# 3_BackBone.net
KiCad netlist of a schematic drawn in Altium Designer
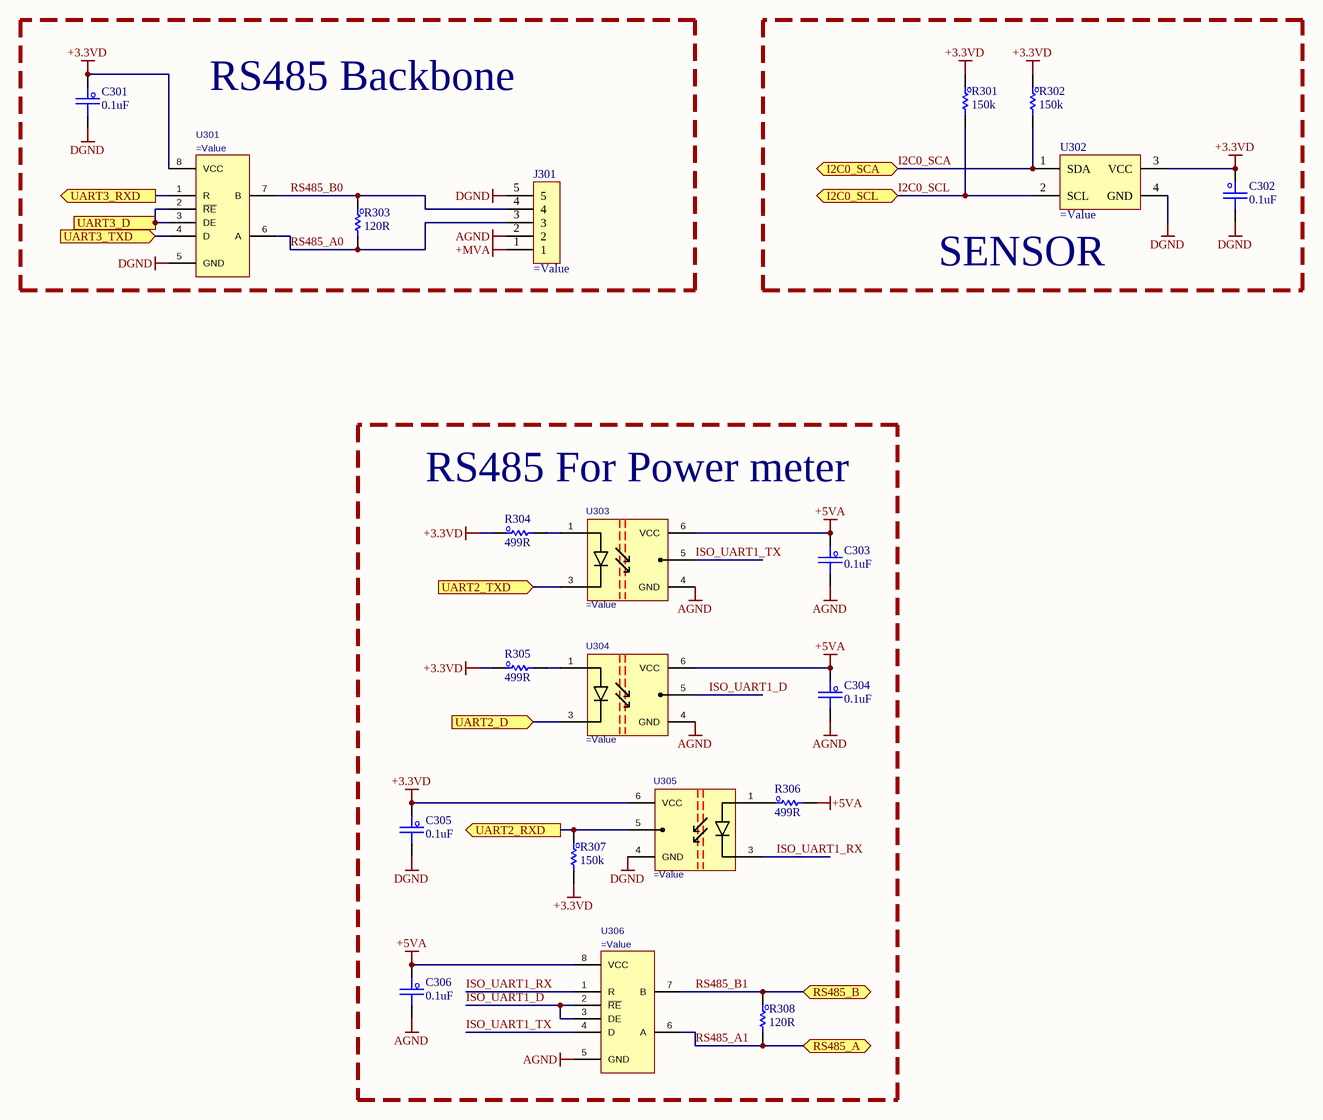
[diagram p0: 3_BackBone.SchDoc]

(export (version "E")
  (design (tool "Eeschema 10.0.6"))
  (components
    (comp (ref "C301")
      (value "0.1uF")
      (footprint "C_0603")
      (description "CAP CER 0.1UF 50V X7R 0603")
      (fields (field (name "MANUFACTURER") "KEMET") (field (name "PARTNUMBER") "C0603C104K5RACTU"))
      (libsource (lib "UUSymbol") (part "C_Capacitor"))
    )
    (comp (ref "C302")
      (value "0.1uF")
      (footprint "C_0603")
      (description "CAP CER 0.1UF 50V X7R 0603")
      (fields (field (name "MANUFACTURER") "KEMET") (field (name "PARTNUMBER") "C0603C104K5RACTU"))
      (libsource (lib "UUSymbol") (part "C_Capacitor"))
    )
    (comp (ref "C303")
      (value "0.1uF")
      (footprint "C_0603")
      (description "CAP CER 0.1UF 50V X7R 0603")
      (fields (field (name "MANUFACTURER") "KEMET") (field (name "PARTNUMBER") "C0603C104K5RACTU"))
      (libsource (lib "UUSymbol") (part "C_Capacitor"))
    )
    (comp (ref "C304")
      (value "0.1uF")
      (footprint "C_0603")
      (description "CAP CER 0.1UF 50V X7R 0603")
      (fields (field (name "MANUFACTURER") "KEMET") (field (name "PARTNUMBER") "C0603C104K5RACTU"))
      (libsource (lib "UUSymbol") (part "C_Capacitor"))
    )
    (comp (ref "C305")
      (value "0.1uF")
      (footprint "C_0603")
      (description "CAP CER 0.1UF 50V X7R 0603")
      (fields (field (name "MANUFACTURER") "KEMET") (field (name "PARTNUMBER") "C0603C104K5RACTU"))
      (libsource (lib "UUSymbol") (part "C_Capacitor"))
    )
    (comp (ref "C306")
      (value "0.1uF")
      (footprint "C_0603")
      (description "CAP CER 0.1UF 50V X7R 0603")
      (fields (field (name "MANUFACTURER") "KEMET") (field (name "PARTNUMBER") "C0603C104K5RACTU"))
      (libsource (lib "UUSymbol") (part "C_Capacitor"))
    )
    (comp (ref "J301")
      (value "~")
      (footprint "CON_9155005541006")
      (description "CONN SPRING BATTERY 5POS R/A SMD")
      (fields (field (name "PARTNUMBER") "009155005541006") (field (name "MANUFACTURER") "AVX"))
      (libsource (lib "UUSymbol") (part "CON_5P_9155005541006"))
    )
    (comp (ref "R301")
      (value "150k")
      (footprint "R_0603")
      (description "RES SMD 150K OHM 1% 1/10W 0603")
      (fields (field (name "MANUFACTURER") "Vishay Dale") (field (name "PARTNUMBER") "CRCW0603150KFKEAC"))
      (libsource (lib "UUSymbol") (part "R_Resister"))
    )
    (comp (ref "R302")
      (value "150k")
      (footprint "R_0603")
      (description "RES SMD 150K OHM 1% 1/10W 0603")
      (fields (field (name "MANUFACTURER") "Vishay Dale") (field (name "PARTNUMBER") "CRCW0603150KFKEAC"))
      (libsource (lib "UUSymbol") (part "R_Resister"))
    )
    (comp (ref "R303")
      (value "120R")
      (footprint "R_0603")
      (description "RES SMD 120 OHM 1% 1/3W 0603")
      (fields (field (name "MANUFACTURER") "Vishay Dale") (field (name "PARTNUMBER") "CRCW0603120RFKEAHP"))
      (libsource (lib "UUSymbol") (part "R_Resister"))
    )
    (comp (ref "R304")
      (value "499R")
      (footprint "R_0603")
      (description "RES 499 OHM 1% 1/10W 0603")
      (fields (field (name "MANUFACTURER") "Vishay Dale") (field (name "PARTNUMBER") "CRCW0603499RFKEAC"))
      (libsource (lib "UUSymbol") (part "R_Resister"))
    )
    (comp (ref "R305")
      (value "499R")
      (footprint "R_0603")
      (description "RES 499 OHM 1% 1/10W 0603")
      (fields (field (name "MANUFACTURER") "Vishay Dale") (field (name "PARTNUMBER") "CRCW0603499RFKEAC"))
      (libsource (lib "UUSymbol") (part "R_Resister"))
    )
    (comp (ref "R306")
      (value "499R")
      (footprint "R_0603")
      (description "RES 499 OHM 1% 1/10W 0603")
      (fields (field (name "MANUFACTURER") "Vishay Dale") (field (name "PARTNUMBER") "CRCW0603499RFKEAC"))
      (libsource (lib "UUSymbol") (part "R_Resister"))
    )
    (comp (ref "R307")
      (value "150k")
      (footprint "R_0603")
      (description "RES SMD 150K OHM 1% 1/10W 0603")
      (fields (field (name "MANUFACTURER") "Vishay Dale") (field (name "PARTNUMBER") "CRCW0603150KFKEAC"))
      (libsource (lib "UUSymbol") (part "R_Resister"))
    )
    (comp (ref "R308")
      (value "120R")
      (footprint "R_0603")
      (description "RES SMD 120 OHM 1% 1/3W 0603")
      (fields (field (name "MANUFACTURER") "Vishay Dale") (field (name "PARTNUMBER") "CRCW0603120RFKEAHP"))
      (libsource (lib "UUSymbol") (part "R_Resister"))
    )
    (comp (ref "U301")
      (value "~")
      (footprint "D0008A_L")
      (description "IC TRANSCEIVER HALF 1/1 8SOIC")
      (fields (field (name "MANUFACTURER") "Texas Instruments") (field (name "PARTNUMBER") "SN65HVD11DR"))
      (libsource (lib "UUSymbol") (part "IC_TRAN_THVD1505DR"))
    )
    (comp (ref "U302")
      (value "~")
      (footprint "XDCR_SHT40-AD1B-R2")
      (description "SENSOR HUMIDITY 100 RH SMD")
      (fields (field (name "PARTNUMBER") "SHT40-AD1B-R3") (field (name "MANUFACTURER") "Sensirion AG"))
      (libsource (lib "UUSymbol") (part "IC_SEN_SHT40-AD1B-R3"))
    )
    (comp (ref "U303")
      (value "~")
      (footprint "5PIN SO6_TOS")
      (description "OPTOISO 5KV PUSH PULL SO6L")
      (fields
        (field (name "MANUFACTURER") "Toshiba Semiconductor and Storage")
        (field (name "PARTNUMBER") "TLP2362(TPL,E(T")
      )
      (libsource (lib "UUSymbol") (part "IC_OPTO_TLP109(TPR,E)"))
    )
    (comp (ref "U304")
      (value "~")
      (footprint "5PIN SO6_TOS")
      (description "OPTOISO 5KV PUSH PULL SO6L")
      (fields
        (field (name "MANUFACTURER") "Toshiba Semiconductor and Storage")
        (field (name "PARTNUMBER") "TLP2362(TPL,E(T")
      )
      (libsource (lib "UUSymbol") (part "IC_OPTO_TLP109(TPR,E)"))
    )
    (comp (ref "U305")
      (value "~")
      (footprint "5PIN SO6_TOS")
      (description "OPTOISO 5KV PUSH PULL SO6L")
      (fields
        (field (name "MANUFACTURER") "Toshiba Semiconductor and Storage")
        (field (name "PARTNUMBER") "TLP2362(TPL,E(T")
      )
      (libsource (lib "") (part "IC_OPTO_TLP109(TPR,E)_1"))
    )
    (comp (ref "U306")
      (value "~")
      (footprint "D0008A_L")
      (description "IC TRANSCEIVER HALF 1/1 8SOIC")
      (fields (field (name "MANUFACTURER") "Texas Instruments") (field (name "PARTNUMBER") "SN75176BDR"))
      (libsource (lib "UUSymbol") (part "IC_TRAN_THVD1505DR"))
    )
  )
  (nets
    (net (code "1") (name "+3.3VD") (class "Default")
      (node (ref "C301") (pin "1") (pinfunction "1_1") (pintype "passive"))
      (node (ref "C302") (pin "1") (pinfunction "1_1") (pintype "passive"))
      (node (ref "C305") (pin "1") (pinfunction "1_1") (pintype "passive"))
      (node (ref "R301") (pin "1") (pinfunction "1_1") (pintype "passive"))
      (node (ref "R302") (pin "1") (pinfunction "1_1") (pintype "passive"))
      (node (ref "R304") (pin "1") (pinfunction "1_1") (pintype "passive"))
      (node (ref "R305") (pin "1") (pinfunction "1_1") (pintype "passive"))
      (node (ref "R307") (pin "2") (pinfunction "2_2") (pintype "passive"))
      (node (ref "U301") (pin "8") (pinfunction "VCC_8") (pintype "passive"))
      (node (ref "U302") (pin "3") (pinfunction "VCC_3") (pintype "passive"))
      (node (ref "U305") (pin "6") (pinfunction "VCC_6") (pintype "passive"))
    )
    (net (code "2") (name "+5VA") (class "Default")
      (node (ref "C303") (pin "1") (pinfunction "1_1") (pintype "passive"))
      (node (ref "C304") (pin "1") (pinfunction "1_1") (pintype "passive"))
      (node (ref "C306") (pin "1") (pinfunction "1_1") (pintype "passive"))
      (node (ref "R306") (pin "2") (pinfunction "2_2") (pintype "passive"))
      (node (ref "U303") (pin "6") (pinfunction "VCC_6") (pintype "passive"))
      (node (ref "U304") (pin "6") (pinfunction "VCC_6") (pintype "passive"))
      (node (ref "U306") (pin "8") (pinfunction "VCC_8") (pintype "passive"))
    )
    (net (code "3") (name "+MVA") (class "Default")
      (node (ref "J301") (pin "1") (pinfunction "1_1") (pintype "passive"))
    )
    (net (code "4") (name "/I2C0_SCA") (class "Default")
      (node (ref "R302") (pin "2") (pinfunction "2_2") (pintype "passive"))
      (node (ref "U302") (pin "1") (pinfunction "SDA_1") (pintype "passive"))
    )
    (net (code "5") (name "/I2C0_SCL") (class "Default")
      (node (ref "R301") (pin "2") (pinfunction "2_2") (pintype "passive"))
      (node (ref "U302") (pin "2") (pinfunction "SCL_2") (pintype "passive"))
    )
    (net (code "6") (name "/ISO_UART1_D") (class "Default")
      (node (ref "U304") (pin "5") (pinfunction "O1_5") (pintype "passive"))
      (node (ref "U306") (pin "2") (pinfunction "~{RE}_2") (pintype "passive"))
      (node (ref "U306") (pin "3") (pinfunction "DE_3") (pintype "passive"))
    )
    (net (code "7") (name "/ISO_UART1_RX") (class "Default")
      (node (ref "U305") (pin "3") (pinfunction "A_3") (pintype "passive"))
      (node (ref "U306") (pin "1") (pinfunction "R_1") (pintype "passive"))
    )
    (net (code "8") (name "/ISO_UART1_TX") (class "Default")
      (node (ref "U303") (pin "5") (pinfunction "O1_5") (pintype "passive"))
      (node (ref "U306") (pin "4") (pinfunction "D_4") (pintype "passive"))
    )
    (net (code "9") (name "/RS485_A0") (class "Default")
      (node (ref "J301") (pin "3") (pinfunction "3_3") (pintype "passive"))
      (node (ref "R303") (pin "2") (pinfunction "2_2") (pintype "passive"))
      (node (ref "U301") (pin "6") (pinfunction "A_6") (pintype "passive"))
    )
    (net (code "10") (name "/RS485_A1") (class "Default")
      (node (ref "R308") (pin "2") (pinfunction "2_2") (pintype "passive"))
      (node (ref "U306") (pin "6") (pinfunction "A_6") (pintype "passive"))
    )
    (net (code "11") (name "/RS485_B0") (class "Default")
      (node (ref "J301") (pin "4") (pinfunction "4_4") (pintype "passive"))
      (node (ref "R303") (pin "1") (pinfunction "1_1") (pintype "passive"))
      (node (ref "U301") (pin "7") (pinfunction "B_7") (pintype "passive"))
    )
    (net (code "12") (name "/RS485_B1") (class "Default")
      (node (ref "R308") (pin "1") (pinfunction "1_1") (pintype "passive"))
      (node (ref "U306") (pin "7") (pinfunction "B_7") (pintype "passive"))
    )
    (net (code "13") (name "/UART2_D") (class "Default")
      (node (ref "U304") (pin "3") (pinfunction "A_3") (pintype "passive"))
    )
    (net (code "14") (name "/UART2_RXD") (class "Default")
      (node (ref "R307") (pin "1") (pinfunction "1_1") (pintype "passive"))
      (node (ref "U305") (pin "5") (pinfunction "O1_5") (pintype "passive"))
    )
    (net (code "15") (name "/UART2_TXD") (class "Default")
      (node (ref "U303") (pin "3") (pinfunction "A_3") (pintype "passive"))
    )
    (net (code "16") (name "/UART3_D") (class "Default")
      (node (ref "U301") (pin "2") (pinfunction "~{RE}_2") (pintype "passive"))
      (node (ref "U301") (pin "3") (pinfunction "DE_3") (pintype "passive"))
    )
    (net (code "17") (name "/UART3_RXD") (class "Default")
      (node (ref "U301") (pin "1") (pinfunction "R_1") (pintype "passive"))
    )
    (net (code "18") (name "/UART3_TXD") (class "Default")
      (node (ref "U301") (pin "4") (pinfunction "D_4") (pintype "passive"))
    )
    (net (code "19") (name "AGND") (class "Default")
      (node (ref "C303") (pin "2") (pinfunction "2_2") (pintype "passive"))
      (node (ref "C304") (pin "2") (pinfunction "2_2") (pintype "passive"))
      (node (ref "C306") (pin "2") (pinfunction "2_2") (pintype "passive"))
      (node (ref "J301") (pin "2") (pinfunction "2_2") (pintype "passive"))
      (node (ref "U303") (pin "4") (pinfunction "GND_4") (pintype "passive"))
      (node (ref "U304") (pin "4") (pinfunction "GND_4") (pintype "passive"))
      (node (ref "U306") (pin "5") (pinfunction "GND_5") (pintype "passive"))
    )
    (net (code "20") (name "DGND") (class "Default")
      (node (ref "C301") (pin "2") (pinfunction "2_2") (pintype "passive"))
      (node (ref "C302") (pin "2") (pinfunction "2_2") (pintype "passive"))
      (node (ref "C305") (pin "2") (pinfunction "2_2") (pintype "passive"))
      (node (ref "J301") (pin "5") (pinfunction "5_5") (pintype "passive"))
      (node (ref "U301") (pin "5") (pinfunction "GND_5") (pintype "passive"))
      (node (ref "U302") (pin "4") (pinfunction "GND_4") (pintype "passive"))
      (node (ref "U305") (pin "4") (pinfunction "GND_4") (pintype "passive"))
    )
    (net (code "21") (name "Net-(R304-Pad2)") (class "Default")
      (node (ref "R304") (pin "2") (pinfunction "2_2") (pintype "passive"))
      (node (ref "U303") (pin "1") (pinfunction "A_1") (pintype "passive"))
    )
    (net (code "22") (name "Net-(R305-Pad2)") (class "Default")
      (node (ref "R305") (pin "2") (pinfunction "2_2") (pintype "passive"))
      (node (ref "U304") (pin "1") (pinfunction "A_1") (pintype "passive"))
    )
    (net (code "23") (name "Net-(R306-Pad1)") (class "Default")
      (node (ref "R306") (pin "1") (pinfunction "1_1") (pintype "passive"))
      (node (ref "U305") (pin "1") (pinfunction "A_1") (pintype "passive"))
    )
  )
)
